# ConectoresEntrada.net
KiCad netlist of a schematic drawn in Altium Designer
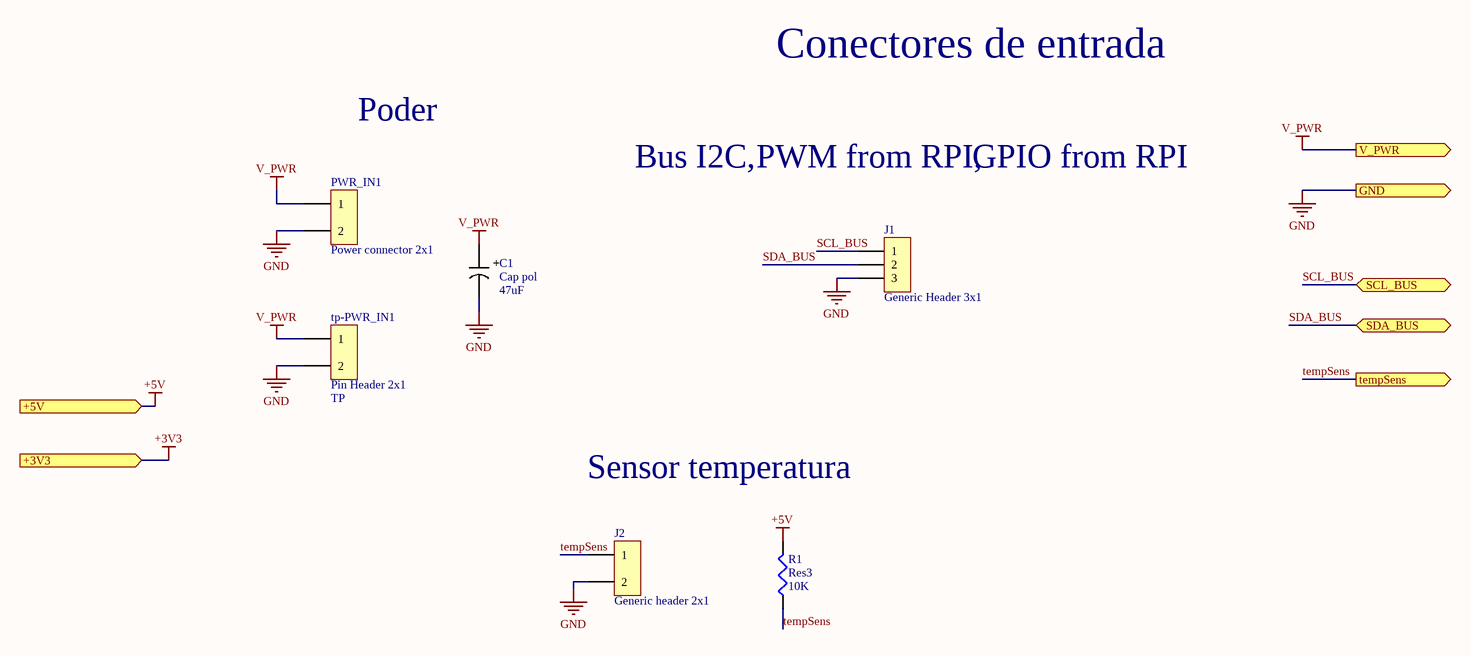
[diagram p0: ConectoresEntrada.SchDoc]

(export (version "E")
  (design (tool "Eeschema 10.0.6"))
  (components
    (comp (ref "C1")
      (value "Cap pol")
      (footprint "CAP_SMD_Electrolytic_10x10")
      (description "Electrolytic Aluminium Capacitor")
      (fields
        (field (name "MANUFACTURER") "Lelon")
        (field (name "MANUFACTURER PART NUMBER") "VEJ470M1HTR-1010")
        (field (name "ALTIUM_VALUE") "47uF")
      )
      (libsource (lib "IoWLabs") (part "Cap pol"))
    )
    (comp (ref "J1")
      (value "Generic Header 3x1")
      (footprint "CONN-TH_A2547WV-3P")
      (description "Generic Header 3pos, 1 row, 2.54 pitch")
      (fields
        (field (name "MANUFACTURER") "CJT(Changjiang Connectors)")
        (field (name "MANUFACTURER PART NUMBER") "A2547WV-3P")
      )
      (libsource (lib "IoWLabsConnectors") (part "Header - 3x1"))
    )
    (comp (ref "J2")
      (value "Generic header 2x1")
      (footprint "CONN-TH_A2547WV-2P")
      (description "Generic Header 2pos, 1 row, 2.54 pitch")
      (fields
        (field (name "MANUFACTURER") "CJT(Changjiang Connectors)")
        (field (name "MANUFACTURER PART NUMBER") "A2547WV-2P")
      )
      (libsource (lib "IoWLabsConnectors") (part "Header - 2x1"))
    )
    (comp (ref "PWR_IN1")
      (value "Power connector 2x1")
      (footprint "CONN-TH_430450212")
      (description "Generic Header Power 2pos")
      (fields (field (name "MANUFACTURER") "MOLEX") (field (name "MANUFACTURER PART NUMBER") "430450212"))
      (libsource (lib "IoWLabsConnectors") (part "PC - 2X1"))
    )
    (comp (ref "R1")
      (value "Res3")
      (footprint "J1-0603")
      (description "Resistor")
      (fields
        (field (name "ALTIUM_VALUE") "10K")
        (field (name "MANUFACTURER") "PANASONIC")
        (field (name "MANUFACTURER PART NUMBER") "ERJPA3F1002V")
        (field (name "PUBLISHER") "Altium Limited")
      )
      (libsource (lib "Miscellaneous Devices") (part "Res3"))
    )
    (comp (ref "tp-PWR_IN1")
      (value "Pin Header 2x1")
      (footprint "HDR-TH_P2.54-H-M_A2541WV-2P")
      (description "Pin Header 2pos, 1 row, 2.54 pitch")
      (fields
        (field (name "MANUFACTURER") "CJT(Changjiang Connectors)")
        (field (name "MANUFACTURER PART NUMBER") "A2541WV-2P")
      )
      (libsource (lib "IoWLabsConnectors") (part "Header - 2x1c"))
    )
  )
  (nets
    (net (code "2") (name "+5V") (class "Default")
      (node (ref "R1") (pin "2") (pinfunction "2_2") (pintype "passive"))
    )
    (net (code "3") (name "/SCL_BUS") (class "Default")
      (node (ref "J1") (pin "1") (pinfunction "1_1") (pintype "passive"))
    )
    (net (code "4") (name "/SDA_BUS") (class "Default")
      (node (ref "J1") (pin "2") (pinfunction "2_2") (pintype "passive"))
    )
    (net (code "5") (name "/tempSens") (class "Default")
      (node (ref "J2") (pin "1") (pinfunction "1_1") (pintype "passive"))
      (node (ref "R1") (pin "1") (pinfunction "1_1") (pintype "passive"))
    )
    (net (code "6") (name "GND") (class "Default")
      (node (ref "C1") (pin "1") (pinfunction "1_1") (pintype "passive"))
      (node (ref "J1") (pin "3") (pinfunction "3_3") (pintype "passive"))
      (node (ref "J2") (pin "2") (pinfunction "2_2") (pintype "passive"))
      (node (ref "PWR_IN1") (pin "2") (pinfunction "2_2") (pintype "passive"))
      (node (ref "tp-PWR_IN1") (pin "2") (pinfunction "2_2") (pintype "passive"))
    )
    (net (code "7") (name "V_PWR") (class "Default")
      (node (ref "C1") (pin "2") (pinfunction "2_2") (pintype "passive"))
      (node (ref "PWR_IN1") (pin "1") (pinfunction "1_1") (pintype "passive"))
      (node (ref "tp-PWR_IN1") (pin "1") (pinfunction "1_1") (pintype "passive"))
    )
  )
)
